# FPGA_OUTPUTS.net
KiCad netlist of a schematic drawn in Altium Designer
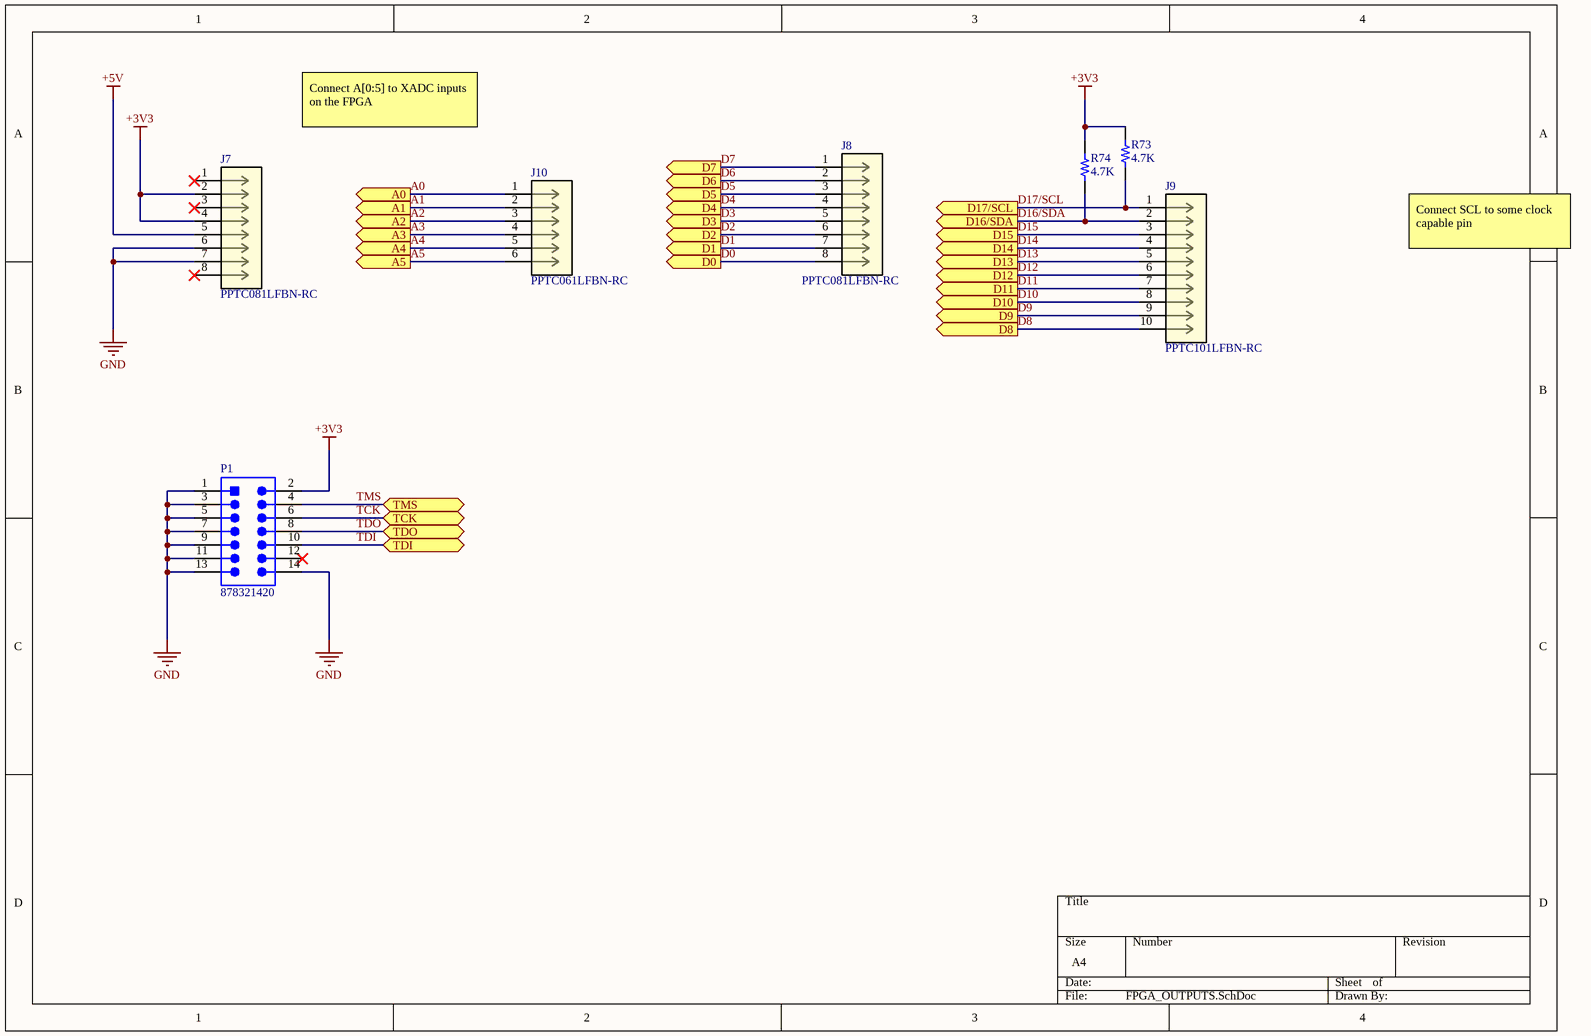
[diagram p0: FPGA_OUTPUTS.SchDoc]

(export (version "E")
  (design (tool "Eeschema 10.0.6"))
  (components
    (comp (ref "J7")
      (value "PPTC081LFBN-RC")
      (footprint "CONN_PPTC081LFBN-RC_SUL")
      (description "No Description Available")
      (libsource (lib "BIG_FPGA") (part "PPTC081LFBN-RC"))
    )
    (comp (ref "J8")
      (value "PPTC081LFBN-RC")
      (footprint "CONN_PPTC081LFBN-RC_SUL")
      (description "No Description Available")
      (libsource (lib "BIG_FPGA") (part "PPTC081LFBN-RC"))
    )
    (comp (ref "J9")
      (value "PPTC101LFBN-RC")
      (footprint "CONN10_101LFBN-RC_SUL")
      (description "No Description Available")
      (libsource (lib "BIG_FPGA") (part "PPTC101LFBN-RC"))
    )
    (comp (ref "J10")
      (value "PPTC061LFBN-RC")
      (footprint "SULLINS_PPTC061LFBN-RC")
      (description "6 Position Header Connector 0.100 (2.54mm) Through Hole Tin")
      (fields (field (name "MF") "Sullins Connector"))
      (libsource (lib "BIG_FPGA") (part "PPTC061LFBN-RC"))
    )
    (comp (ref "P1")
      (value "878321420")
      (footprint "MOLX-878321420_V")
      (description "Male Header, Pitch 2 mm, 2 x 7 Position, Height 7.6 mm, -55 to 105 degC, RoHS")
      (fields (field (name "MANUFACTURER") "Molex"))
      (libsource (lib "Altium Content Vault") (part "CN-2P-M-R14"))
    )
    (comp (ref "R73")
      (value "4.7K")
      (footprint "RES 0603_1608")
      (libsource (lib "Midnight Sun") (part "Resistor"))
    )
    (comp (ref "R74")
      (value "4.7K")
      (footprint "RES 0603_1608")
      (libsource (lib "Midnight Sun") (part "Resistor"))
    )
  )
  (nets
    (net (code "1") (name "+3V3") (class "Default")
      (node (ref "J7") (pin "2") (pinfunction "2_2") (pintype "passive"))
      (node (ref "J7") (pin "4") (pinfunction "4_4") (pintype "passive"))
      (node (ref "P1") (pin "2") (pinfunction "2_2") (pintype "passive"))
      (node (ref "R73") (pin "2") (pinfunction "2_2") (pintype "passive"))
      (node (ref "R74") (pin "2") (pinfunction "2_2") (pintype "passive"))
    )
    (net (code "2") (name "+5V") (class "Default")
      (node (ref "J7") (pin "5") (pinfunction "5_5") (pintype "passive"))
    )
    (net (code "3") (name "/A0") (class "Default")
      (node (ref "J10") (pin "1") (pinfunction "1_1") (pintype "passive"))
    )
    (net (code "4") (name "/A1") (class "Default")
      (node (ref "J10") (pin "2") (pinfunction "2_2") (pintype "passive"))
    )
    (net (code "5") (name "/A2") (class "Default")
      (node (ref "J10") (pin "3") (pinfunction "3_3") (pintype "passive"))
    )
    (net (code "6") (name "/A3") (class "Default")
      (node (ref "J10") (pin "4") (pinfunction "4_4") (pintype "passive"))
    )
    (net (code "7") (name "/A4") (class "Default")
      (node (ref "J10") (pin "5") (pinfunction "5_5") (pintype "passive"))
    )
    (net (code "8") (name "/A5") (class "Default")
      (node (ref "J10") (pin "6") (pinfunction "6_6") (pintype "passive"))
    )
    (net (code "9") (name "/D0") (class "Default")
      (node (ref "J8") (pin "8") (pinfunction "8_8") (pintype "passive"))
    )
    (net (code "10") (name "/D1") (class "Default")
      (node (ref "J8") (pin "7") (pinfunction "7_7") (pintype "passive"))
    )
    (net (code "11") (name "/D2") (class "Default")
      (node (ref "J8") (pin "6") (pinfunction "6_6") (pintype "passive"))
    )
    (net (code "12") (name "/D3") (class "Default")
      (node (ref "J8") (pin "5") (pinfunction "5_5") (pintype "passive"))
    )
    (net (code "13") (name "/D4") (class "Default")
      (node (ref "J8") (pin "4") (pinfunction "4_4") (pintype "passive"))
    )
    (net (code "14") (name "/D5") (class "Default")
      (node (ref "J8") (pin "3") (pinfunction "3_3") (pintype "passive"))
    )
    (net (code "15") (name "/D6") (class "Default")
      (node (ref "J8") (pin "2") (pinfunction "2_2") (pintype "passive"))
    )
    (net (code "16") (name "/D7") (class "Default")
      (node (ref "J8") (pin "1") (pinfunction "1_1") (pintype "passive"))
    )
    (net (code "17") (name "/D8") (class "Default")
      (node (ref "J9") (pin "10") (pinfunction "10_10") (pintype "passive"))
    )
    (net (code "18") (name "/D9") (class "Default")
      (node (ref "J9") (pin "9") (pinfunction "9_9") (pintype "passive"))
    )
    (net (code "19") (name "/D10") (class "Default")
      (node (ref "J9") (pin "8") (pinfunction "8_8") (pintype "passive"))
    )
    (net (code "20") (name "/D11") (class "Default")
      (node (ref "J9") (pin "7") (pinfunction "7_7") (pintype "passive"))
    )
    (net (code "21") (name "/D12") (class "Default")
      (node (ref "J9") (pin "6") (pinfunction "6_6") (pintype "passive"))
    )
    (net (code "22") (name "/D13") (class "Default")
      (node (ref "J9") (pin "5") (pinfunction "5_5") (pintype "passive"))
    )
    (net (code "23") (name "/D14") (class "Default")
      (node (ref "J9") (pin "4") (pinfunction "4_4") (pintype "passive"))
    )
    (net (code "24") (name "/D15") (class "Default")
      (node (ref "J9") (pin "3") (pinfunction "3_3") (pintype "passive"))
    )
    (net (code "25") (name "/D16{slash}SDA") (class "Default")
      (node (ref "J9") (pin "2") (pinfunction "2_2") (pintype "passive"))
      (node (ref "R74") (pin "1") (pinfunction "1_1") (pintype "passive"))
    )
    (net (code "26") (name "/D17{slash}SCL") (class "Default")
      (node (ref "J9") (pin "1") (pinfunction "1_1") (pintype "passive"))
      (node (ref "R73") (pin "1") (pinfunction "1_1") (pintype "passive"))
    )
    (net (code "27") (name "/TCK") (class "Default")
      (node (ref "P1") (pin "6") (pinfunction "6_6") (pintype "passive"))
    )
    (net (code "28") (name "/TDI") (class "Default")
      (node (ref "P1") (pin "10") (pinfunction "10_10") (pintype "passive"))
    )
    (net (code "29") (name "/TDO") (class "Default")
      (node (ref "P1") (pin "8") (pinfunction "8_8") (pintype "passive"))
    )
    (net (code "30") (name "/TMS") (class "Default")
      (node (ref "P1") (pin "4") (pinfunction "4_4") (pintype "passive"))
    )
    (net (code "31") (name "GND") (class "Default")
      (node (ref "J7") (pin "6") (pinfunction "6_6") (pintype "passive"))
      (node (ref "J7") (pin "7") (pinfunction "7_7") (pintype "passive"))
      (node (ref "P1") (pin "1") (pinfunction "1_1") (pintype "passive"))
      (node (ref "P1") (pin "11") (pinfunction "11_11") (pintype "passive"))
      (node (ref "P1") (pin "13") (pinfunction "13_13") (pintype "passive"))
      (node (ref "P1") (pin "14") (pinfunction "14_14") (pintype "passive"))
      (node (ref "P1") (pin "3") (pinfunction "3_3") (pintype "passive"))
      (node (ref "P1") (pin "5") (pinfunction "5_5") (pintype "passive"))
      (node (ref "P1") (pin "7") (pinfunction "7_7") (pintype "passive"))
      (node (ref "P1") (pin "9") (pinfunction "9_9") (pintype "passive"))
    )
    (net (code "32") (name "unconnected-(J7-Pad1)") (class "Default")
      (node (ref "J7") (pin "1") (pinfunction "1_1") (pintype "passive+no_connect"))
    )
    (net (code "33") (name "unconnected-(J7-Pad3)") (class "Default")
      (node (ref "J7") (pin "3") (pinfunction "3_3") (pintype "passive+no_connect"))
    )
    (net (code "34") (name "unconnected-(J7-Pad8)") (class "Default")
      (node (ref "J7") (pin "8") (pinfunction "8_8") (pintype "passive+no_connect"))
    )
    (net (code "35") (name "unconnected-(P1-Pad12)") (class "Default")
      (node (ref "P1") (pin "12") (pinfunction "12_12") (pintype "passive+no_connect"))
    )
  )
)
